# main_v3.net
KiCad netlist of a schematic drawn in EAGLE
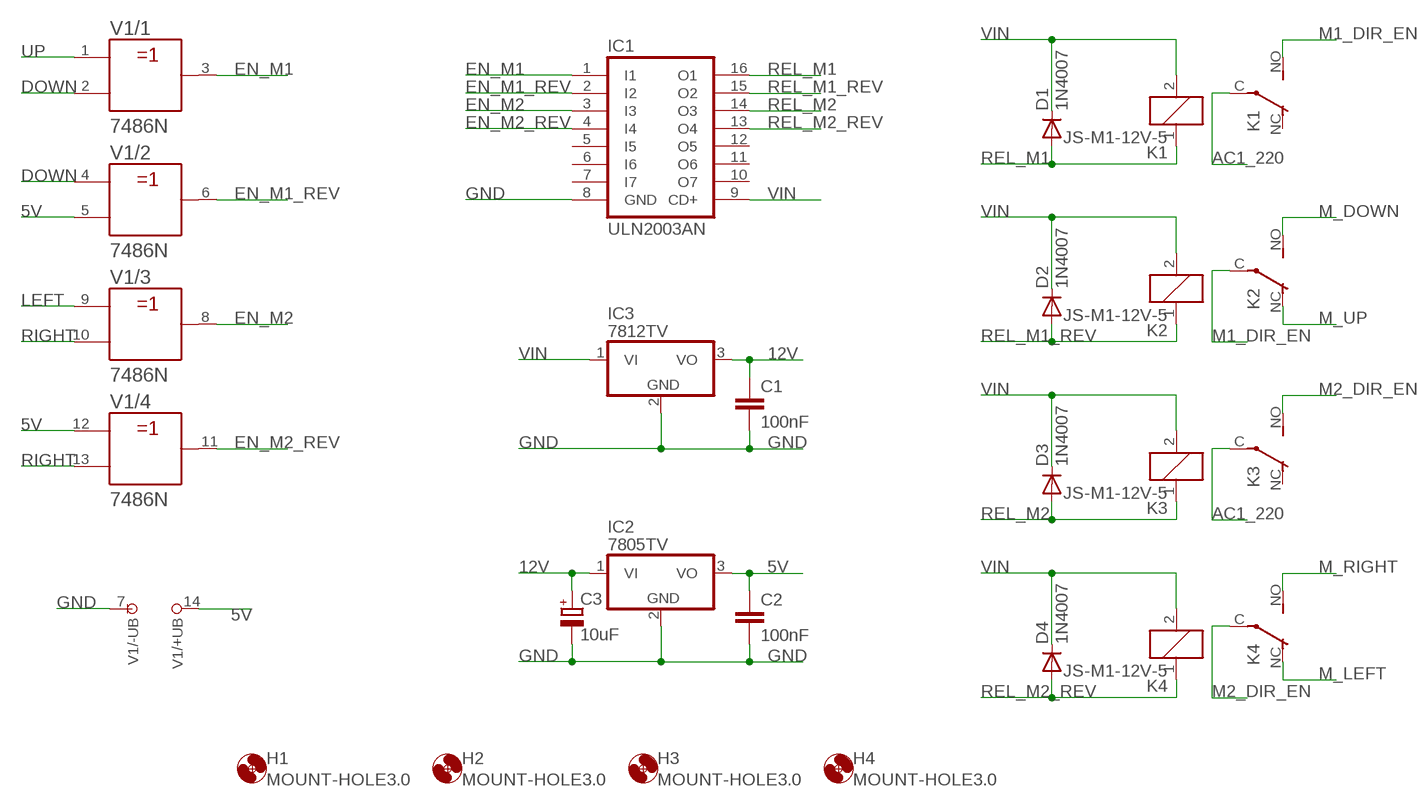
[diagram p0: schematic, sheet 1]
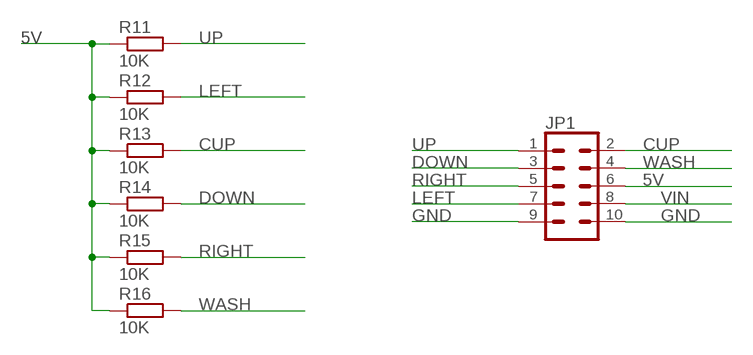
[diagram p1: schematic, sheet 2]
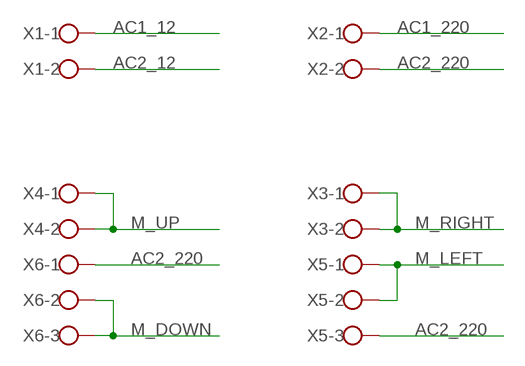
[diagram p2: schematic, sheet 3]
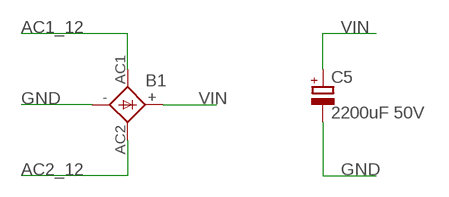
[diagram p3: schematic, sheet 4]
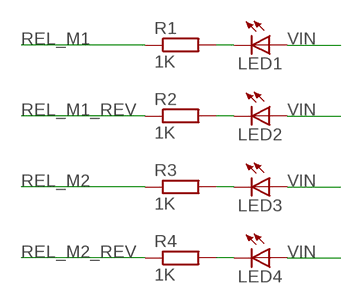
[diagram p4: schematic, sheet 5]

(export (version "E")
  (design (tool "Eeschema 10.0.6"))
  (components
    (comp (ref "X1")
      (value "W237-102")
      (footprint "eagle-import:W237-102")
      (libsource (lib "eagle-import") (part "W237-102"))
    )
    (comp (ref "X2")
      (value "W237-102")
      (footprint "eagle-import:W237-102")
      (libsource (lib "eagle-import") (part "W237-102"))
    )
    (comp (ref "X3")
      (value "W237-102")
      (footprint "eagle-import:W237-102")
      (libsource (lib "eagle-import") (part "W237-102"))
    )
    (comp (ref "X4")
      (value "W237-102")
      (footprint "eagle-import:W237-102")
      (libsource (lib "eagle-import") (part "W237-102"))
    )
    (comp (ref "X5")
      (value "W237-103")
      (footprint "eagle-import:W237-103")
      (libsource (lib "eagle-import") (part "W237-103"))
    )
    (comp (ref "X6")
      (value "W237-103")
      (footprint "eagle-import:W237-103")
      (libsource (lib "eagle-import") (part "W237-103"))
    )
    (comp (ref "LED1")
      (value "LED5MM")
      (footprint "eagle-import:LED5MM")
      (libsource (lib "eagle-import") (part "LED5MM"))
    )
    (comp (ref "LED2")
      (value "LED5MM")
      (footprint "eagle-import:LED5MM")
      (libsource (lib "eagle-import") (part "LED5MM"))
    )
    (comp (ref "LED3")
      (value "LED5MM")
      (footprint "eagle-import:LED5MM")
      (libsource (lib "eagle-import") (part "LED5MM"))
    )
    (comp (ref "LED4")
      (value "LED5MM")
      (footprint "eagle-import:LED5MM")
      (libsource (lib "eagle-import") (part "LED5MM"))
    )
    (comp (ref "R1")
      (value "1K")
      (footprint "eagle-import:0207_10")
      (libsource (lib "eagle-import") (part "R-EU_0207/10"))
    )
    (comp (ref "R2")
      (value "1K")
      (footprint "eagle-import:0207_10")
      (libsource (lib "eagle-import") (part "R-EU_0207/10"))
    )
    (comp (ref "R3")
      (value "1K")
      (footprint "eagle-import:0207_10")
      (libsource (lib "eagle-import") (part "R-EU_0207/10"))
    )
    (comp (ref "R4")
      (value "1K")
      (footprint "eagle-import:0207_10")
      (libsource (lib "eagle-import") (part "R-EU_0207/10"))
    )
    (comp (ref "JP1")
      (value "CONN_05X2PTH")
      (footprint "eagle-import:2X5")
      (libsource (lib "eagle-import") (part "CONN_05X2PTH"))
    )
    (comp (ref "R11")
      (value "10K")
      (footprint "eagle-import:0207_10")
      (libsource (lib "eagle-import") (part "R-EU_0207/10"))
    )
    (comp (ref "R12")
      (value "10K")
      (footprint "eagle-import:0207_10")
      (libsource (lib "eagle-import") (part "R-EU_0207/10"))
    )
    (comp (ref "R13")
      (value "10K")
      (footprint "eagle-import:0207_10")
      (libsource (lib "eagle-import") (part "R-EU_0207/10"))
    )
    (comp (ref "R14")
      (value "10K")
      (footprint "eagle-import:0207_10")
      (libsource (lib "eagle-import") (part "R-EU_0207/10"))
    )
    (comp (ref "R15")
      (value "10K")
      (footprint "eagle-import:0207_10")
      (libsource (lib "eagle-import") (part "R-EU_0207/10"))
    )
    (comp (ref "R16")
      (value "10K")
      (footprint "eagle-import:0207_10")
      (libsource (lib "eagle-import") (part "R-EU_0207/10"))
    )
    (comp (ref "C1")
      (value "100nF")
      (footprint "eagle-import:C050-025X075")
      (libsource (lib "eagle-import") (part "C-EU050-025X075"))
    )
    (comp (ref "C2")
      (value "100nF")
      (footprint "eagle-import:C050-025X075")
      (libsource (lib "eagle-import") (part "C-EU050-025X075"))
    )
    (comp (ref "C3")
      (value "10uF")
      (footprint "eagle-import:E3,5-8")
      (libsource (lib "eagle-import") (part "rcl_334_CPOL-EUE3.5-8"))
    )
    (comp (ref "D1")
      (value "1N4007")
      (footprint "eagle-import:DO41-10")
      (libsource (lib "eagle-import") (part "1N4004"))
    )
    (comp (ref "D2")
      (value "1N4007")
      (footprint "eagle-import:DO41-10")
      (libsource (lib "eagle-import") (part "1N4004"))
    )
    (comp (ref "D3")
      (value "1N4007")
      (footprint "eagle-import:DO41-10")
      (libsource (lib "eagle-import") (part "1N4004"))
    )
    (comp (ref "D4")
      (value "1N4007")
      (footprint "eagle-import:DO41-10")
      (libsource (lib "eagle-import") (part "1N4004"))
    )
    (comp (ref "H1")
      (value "MOUNT-HOLE3.0")
      (footprint "eagle-import:3,0")
      (libsource (lib "eagle-import") (part "MOUNT-HOLE3.0"))
    )
    (comp (ref "H2")
      (value "MOUNT-HOLE3.0")
      (footprint "eagle-import:3,0")
      (libsource (lib "eagle-import") (part "MOUNT-HOLE3.0"))
    )
    (comp (ref "H3")
      (value "MOUNT-HOLE3.0")
      (footprint "eagle-import:3,0")
      (libsource (lib "eagle-import") (part "MOUNT-HOLE3.0"))
    )
    (comp (ref "H4")
      (value "MOUNT-HOLE3.0")
      (footprint "eagle-import:3,0")
      (libsource (lib "eagle-import") (part "MOUNT-HOLE3.0"))
    )
    (comp (ref "IC1")
      (value "ULN2003AN")
      (footprint "eagle-import:DIL16")
      (libsource (lib "eagle-import") (part "ULN2003AN"))
    )
    (comp (ref "IC2")
      (value "7805TV")
      (footprint "eagle-import:TO220V")
      (libsource (lib "eagle-import") (part "linear_262_78TV05"))
    )
    (comp (ref "IC3")
      (value "7812TV")
      (footprint "eagle-import:TO220V")
      (libsource (lib "eagle-import") (part "78TV12"))
    )
    (comp (ref "K1")
      (value "JS-M1-12V-5")
      (footprint "eagle-import:JS-M")
      (fields (field (name "MF") "FARNELL") (field (name "MPN") "JSM1-12V-5"))
      (libsource (lib "eagle-import") (part "JS-M1-12V-5"))
    )
    (comp (ref "K2")
      (value "JS-M1-12V-5")
      (footprint "eagle-import:JS-M")
      (fields (field (name "MF") "FARNELL") (field (name "MPN") "JSM1-12V-5"))
      (libsource (lib "eagle-import") (part "JS-M1-12V-5"))
    )
    (comp (ref "K3")
      (value "JS-M1-12V-5")
      (footprint "eagle-import:JS-M")
      (fields (field (name "MF") "FARNELL") (field (name "MPN") "JSM1-12V-5"))
      (libsource (lib "eagle-import") (part "JS-M1-12V-5"))
    )
    (comp (ref "K4")
      (value "JS-M1-12V-5")
      (footprint "eagle-import:JS-M")
      (fields (field (name "MF") "FARNELL") (field (name "MPN") "JSM1-12V-5"))
      (libsource (lib "eagle-import") (part "JS-M1-12V-5"))
    )
    (comp (ref "V1")
      (value "7486N")
      (footprint "eagle-import:DIL14")
      (libsource (lib "eagle-import") (part "7486N"))
    )
    (comp (ref "B1")
      (value "GBPC6")
      (footprint "eagle-import:GBPC6")
      (libsource (lib "eagle-import") (part "GBPC6"))
    )
    (comp (ref "C5")
      (value "2200uF 50V")
      (footprint "eagle-import:E7,5-18")
      (libsource (lib "eagle-import") (part "CPOL-EUE7.5-18"))
    )
  )
  (nets
    (net (code "1") (name "5V") (class "Default")
      (node (ref "C2") (pin "1") (pinfunction "1_1") (pintype "passive"))
      (node (ref "IC2") (pin "3") (pinfunction "VO_3") (pintype "passive"))
      (node (ref "JP1") (pin "6") (pinfunction "6_6") (pintype "passive"))
      (node (ref "R11") (pin "1") (pinfunction "1_1") (pintype "passive"))
      (node (ref "R12") (pin "1") (pinfunction "1_1") (pintype "passive"))
      (node (ref "R13") (pin "1") (pinfunction "1_1") (pintype "passive"))
      (node (ref "R14") (pin "1") (pinfunction "1_1") (pintype "passive"))
      (node (ref "R15") (pin "1") (pinfunction "1_1") (pintype "passive"))
      (node (ref "R16") (pin "1") (pinfunction "1_1") (pintype "passive"))
      (node (ref "V1") (pin "12") (pinfunction "A_12") (pintype "input"))
      (node (ref "V1") (pin "14") (pinfunction "+UB_14") (pintype "power_in"))
      (node (ref "V1") (pin "5") (pinfunction "B_5") (pintype "input"))
    )
    (net (code "2") (name "12V") (class "Default")
      (node (ref "C1") (pin "1") (pinfunction "1_1") (pintype "passive"))
      (node (ref "C3") (pin "+") (pinfunction "+_+") (pintype "passive"))
      (node (ref "IC2") (pin "1") (pinfunction "VI_1") (pintype "input"))
      (node (ref "IC3") (pin "3") (pinfunction "VO_3") (pintype "passive"))
    )
    (net (code "3") (name "AC1_12") (class "Default")
      (node (ref "B1") (pin "AC1") (pinfunction "AC1_AC1") (pintype "passive"))
      (node (ref "X1") (pin "1") (pinfunction "KL_1") (pintype "passive"))
    )
    (net (code "4") (name "AC1_220") (class "Default")
      (node (ref "K1") (pin "C") (pinfunction "P_C") (pintype "passive"))
      (node (ref "K3") (pin "C") (pinfunction "P_C") (pintype "passive"))
      (node (ref "X2") (pin "1") (pinfunction "KL_1") (pintype "passive"))
    )
    (net (code "5") (name "AC2_12") (class "Default")
      (node (ref "B1") (pin "AC2") (pinfunction "AC2_AC2") (pintype "passive"))
      (node (ref "X1") (pin "2") (pinfunction "KL_2") (pintype "passive"))
    )
    (net (code "6") (name "AC2_220") (class "Default")
      (node (ref "X2") (pin "2") (pinfunction "KL_2") (pintype "passive"))
      (node (ref "X5") (pin "3") (pinfunction "KL_3") (pintype "passive"))
      (node (ref "X6") (pin "1") (pinfunction "KL_1") (pintype "passive"))
    )
    (net (code "7") (name "CUP") (class "Default")
      (node (ref "JP1") (pin "2") (pinfunction "2_2") (pintype "passive"))
      (node (ref "R13") (pin "2") (pinfunction "2_2") (pintype "passive"))
    )
    (net (code "8") (name "DOWN") (class "Default")
      (node (ref "JP1") (pin "3") (pinfunction "3_3") (pintype "passive"))
      (node (ref "R14") (pin "2") (pinfunction "2_2") (pintype "passive"))
      (node (ref "V1") (pin "2") (pinfunction "B_2") (pintype "input"))
      (node (ref "V1") (pin "4") (pinfunction "A_4") (pintype "input"))
    )
    (net (code "9") (name "EN_M1") (class "Default")
      (node (ref "IC1") (pin "1") (pinfunction "I1_1") (pintype "input"))
      (node (ref "V1") (pin "3") (pinfunction "Y_3") (pintype "output"))
    )
    (net (code "10") (name "EN_M1_REV") (class "Default")
      (node (ref "IC1") (pin "2") (pinfunction "I2_2") (pintype "input"))
      (node (ref "V1") (pin "6") (pinfunction "Y_6") (pintype "output"))
    )
    (net (code "11") (name "EN_M2") (class "Default")
      (node (ref "IC1") (pin "3") (pinfunction "I3_3") (pintype "input"))
      (node (ref "V1") (pin "8") (pinfunction "Y_8") (pintype "output"))
    )
    (net (code "12") (name "EN_M2_REV") (class "Default")
      (node (ref "IC1") (pin "4") (pinfunction "I4_4") (pintype "input"))
      (node (ref "V1") (pin "11") (pinfunction "Y_11") (pintype "output"))
    )
    (net (code "13") (name "GND") (class "Default")
      (node (ref "B1") (pin "-") (pinfunction "-_-") (pintype "passive"))
      (node (ref "C1") (pin "2") (pinfunction "2_2") (pintype "passive"))
      (node (ref "C2") (pin "2") (pinfunction "2_2") (pintype "passive"))
      (node (ref "C3") (pin "-") (pinfunction "-_-") (pintype "passive"))
      (node (ref "C5") (pin "-") (pinfunction "-_-") (pintype "passive"))
      (node (ref "IC1") (pin "8") (pinfunction "GND_8") (pintype "power_in"))
      (node (ref "IC2") (pin "2") (pinfunction "GND_2") (pintype "passive"))
      (node (ref "IC3") (pin "2") (pinfunction "GND_2") (pintype "passive"))
      (node (ref "JP1") (pin "10") (pinfunction "10_10") (pintype "passive"))
      (node (ref "JP1") (pin "9") (pinfunction "9_9") (pintype "passive"))
      (node (ref "V1") (pin "7") (pinfunction "-UB_7") (pintype "power_in"))
    )
    (net (code "14") (name "LEFT") (class "Default")
      (node (ref "JP1") (pin "7") (pinfunction "7_7") (pintype "passive"))
      (node (ref "R12") (pin "2") (pinfunction "2_2") (pintype "passive"))
      (node (ref "V1") (pin "9") (pinfunction "A_9") (pintype "input"))
    )
    (net (code "15") (name "M1_DIR_EN") (class "Default")
      (node (ref "K1") (pin "NO") (pinfunction "S_NO") (pintype "passive"))
      (node (ref "K2") (pin "C") (pinfunction "P_C") (pintype "passive"))
    )
    (net (code "16") (name "M2_DIR_EN") (class "Default")
      (node (ref "K3") (pin "NO") (pinfunction "S_NO") (pintype "passive"))
      (node (ref "K4") (pin "C") (pinfunction "P_C") (pintype "passive"))
    )
    (net (code "17") (name "M_DOWN") (class "Default")
      (node (ref "K2") (pin "NO") (pinfunction "S_NO") (pintype "passive"))
      (node (ref "X6") (pin "2") (pinfunction "KL_2") (pintype "passive"))
      (node (ref "X6") (pin "3") (pinfunction "KL_3") (pintype "passive"))
    )
    (net (code "18") (name "M_LEFT") (class "Default")
      (node (ref "K4") (pin "NC") (pinfunction "O_NC") (pintype "passive"))
      (node (ref "X5") (pin "1") (pinfunction "KL_1") (pintype "passive"))
      (node (ref "X5") (pin "2") (pinfunction "KL_2") (pintype "passive"))
    )
    (net (code "19") (name "M_RIGHT") (class "Default")
      (node (ref "K4") (pin "NO") (pinfunction "S_NO") (pintype "passive"))
      (node (ref "X3") (pin "1") (pinfunction "KL_1") (pintype "passive"))
      (node (ref "X3") (pin "2") (pinfunction "KL_2") (pintype "passive"))
    )
    (net (code "20") (name "M_UP") (class "Default")
      (node (ref "K2") (pin "NC") (pinfunction "O_NC") (pintype "passive"))
      (node (ref "X4") (pin "1") (pinfunction "KL_1") (pintype "passive"))
      (node (ref "X4") (pin "2") (pinfunction "KL_2") (pintype "passive"))
    )
    (net (code "21") (name "Net-(LED1-C)") (class "Default")
      (node (ref "LED1") (pin "K") (pinfunction "C_K") (pintype "passive"))
      (node (ref "R1") (pin "2") (pinfunction "2_2") (pintype "passive"))
    )
    (net (code "22") (name "Net-(LED2-C)") (class "Default")
      (node (ref "LED2") (pin "K") (pinfunction "C_K") (pintype "passive"))
      (node (ref "R2") (pin "2") (pinfunction "2_2") (pintype "passive"))
    )
    (net (code "23") (name "Net-(LED3-C)") (class "Default")
      (node (ref "LED3") (pin "K") (pinfunction "C_K") (pintype "passive"))
      (node (ref "R3") (pin "2") (pinfunction "2_2") (pintype "passive"))
    )
    (net (code "24") (name "Net-(LED4-C)") (class "Default")
      (node (ref "LED4") (pin "K") (pinfunction "C_K") (pintype "passive"))
      (node (ref "R4") (pin "2") (pinfunction "2_2") (pintype "passive"))
    )
    (net (code "25") (name "REL_M1") (class "Default")
      (node (ref "D1") (pin "A") (pinfunction "A_A") (pintype "passive"))
      (node (ref "IC1") (pin "16") (pinfunction "O1_16") (pintype "open_collector"))
      (node (ref "K1") (pin "1") (pinfunction "1_1") (pintype "passive"))
      (node (ref "R1") (pin "1") (pinfunction "1_1") (pintype "passive"))
    )
    (net (code "26") (name "REL_M1_REV") (class "Default")
      (node (ref "D2") (pin "A") (pinfunction "A_A") (pintype "passive"))
      (node (ref "IC1") (pin "15") (pinfunction "O2_15") (pintype "open_collector"))
      (node (ref "K2") (pin "1") (pinfunction "1_1") (pintype "passive"))
      (node (ref "R2") (pin "1") (pinfunction "1_1") (pintype "passive"))
    )
    (net (code "27") (name "REL_M2") (class "Default")
      (node (ref "D3") (pin "A") (pinfunction "A_A") (pintype "passive"))
      (node (ref "IC1") (pin "14") (pinfunction "O3_14") (pintype "open_collector"))
      (node (ref "K3") (pin "1") (pinfunction "1_1") (pintype "passive"))
      (node (ref "R3") (pin "1") (pinfunction "1_1") (pintype "passive"))
    )
    (net (code "28") (name "REL_M2_REV") (class "Default")
      (node (ref "D4") (pin "A") (pinfunction "A_A") (pintype "passive"))
      (node (ref "IC1") (pin "13") (pinfunction "O4_13") (pintype "open_collector"))
      (node (ref "K4") (pin "1") (pinfunction "1_1") (pintype "passive"))
      (node (ref "R4") (pin "1") (pinfunction "1_1") (pintype "passive"))
    )
    (net (code "29") (name "RIGHT") (class "Default")
      (node (ref "JP1") (pin "5") (pinfunction "5_5") (pintype "passive"))
      (node (ref "R15") (pin "2") (pinfunction "2_2") (pintype "passive"))
      (node (ref "V1") (pin "10") (pinfunction "B_10") (pintype "input"))
      (node (ref "V1") (pin "13") (pinfunction "B_13") (pintype "input"))
    )
    (net (code "30") (name "UP") (class "Default")
      (node (ref "JP1") (pin "1") (pinfunction "1_1") (pintype "passive"))
      (node (ref "R11") (pin "2") (pinfunction "2_2") (pintype "passive"))
      (node (ref "V1") (pin "1") (pinfunction "A_1") (pintype "input"))
    )
    (net (code "31") (name "VIN") (class "Default")
      (node (ref "B1") (pin "+") (pinfunction "+_+") (pintype "passive"))
      (node (ref "C5") (pin "+") (pinfunction "+_+") (pintype "passive"))
      (node (ref "D1") (pin "C") (pinfunction "C_C") (pintype "passive"))
      (node (ref "D2") (pin "C") (pinfunction "C_C") (pintype "passive"))
      (node (ref "D3") (pin "C") (pinfunction "C_C") (pintype "passive"))
      (node (ref "D4") (pin "C") (pinfunction "C_C") (pintype "passive"))
      (node (ref "IC1") (pin "9") (pinfunction "CD+_9") (pintype "passive"))
      (node (ref "IC3") (pin "1") (pinfunction "VI_1") (pintype "input"))
      (node (ref "JP1") (pin "8") (pinfunction "8_8") (pintype "passive"))
      (node (ref "K1") (pin "2") (pinfunction "2_2") (pintype "passive"))
      (node (ref "K2") (pin "2") (pinfunction "2_2") (pintype "passive"))
      (node (ref "K3") (pin "2") (pinfunction "2_2") (pintype "passive"))
      (node (ref "K4") (pin "2") (pinfunction "2_2") (pintype "passive"))
      (node (ref "LED1") (pin "A") (pinfunction "A_A") (pintype "passive"))
      (node (ref "LED2") (pin "A") (pinfunction "A_A") (pintype "passive"))
      (node (ref "LED3") (pin "A") (pinfunction "A_A") (pintype "passive"))
      (node (ref "LED4") (pin "A") (pinfunction "A_A") (pintype "passive"))
    )
    (net (code "32") (name "WASH") (class "Default")
      (node (ref "JP1") (pin "4") (pinfunction "4_4") (pintype "passive"))
      (node (ref "R16") (pin "2") (pinfunction "2_2") (pintype "passive"))
    )
    (net (code "33") (name "unconnected-(IC1-I5-Pad5)") (class "Default")
      (node (ref "IC1") (pin "5") (pinfunction "I5_5") (pintype "input"))
    )
    (net (code "34") (name "unconnected-(IC1-I6-Pad6)") (class "Default")
      (node (ref "IC1") (pin "6") (pinfunction "I6_6") (pintype "input"))
    )
    (net (code "35") (name "unconnected-(IC1-I7-Pad7)") (class "Default")
      (node (ref "IC1") (pin "7") (pinfunction "I7_7") (pintype "input"))
    )
    (net (code "36") (name "unconnected-(IC1-O5-Pad12)") (class "Default")
      (node (ref "IC1") (pin "12") (pinfunction "O5_12") (pintype "open_collector"))
    )
    (net (code "37") (name "unconnected-(IC1-O6-Pad11)") (class "Default")
      (node (ref "IC1") (pin "11") (pinfunction "O6_11") (pintype "open_collector"))
    )
    (net (code "38") (name "unconnected-(IC1-O7-Pad10)") (class "Default")
      (node (ref "IC1") (pin "10") (pinfunction "O7_10") (pintype "open_collector"))
    )
    (net (code "39") (name "unconnected-(K1B-O-PadNC)") (class "Default")
      (node (ref "K1") (pin "NC") (pinfunction "O_NC") (pintype "passive"))
    )
    (net (code "40") (name "unconnected-(K3B-O-PadNC)") (class "Default")
      (node (ref "K3") (pin "NC") (pinfunction "O_NC") (pintype "passive"))
    )
  )
)
